# Spooky_Sound_System.net
KiCad netlist of a schematic drawn in EAGLE
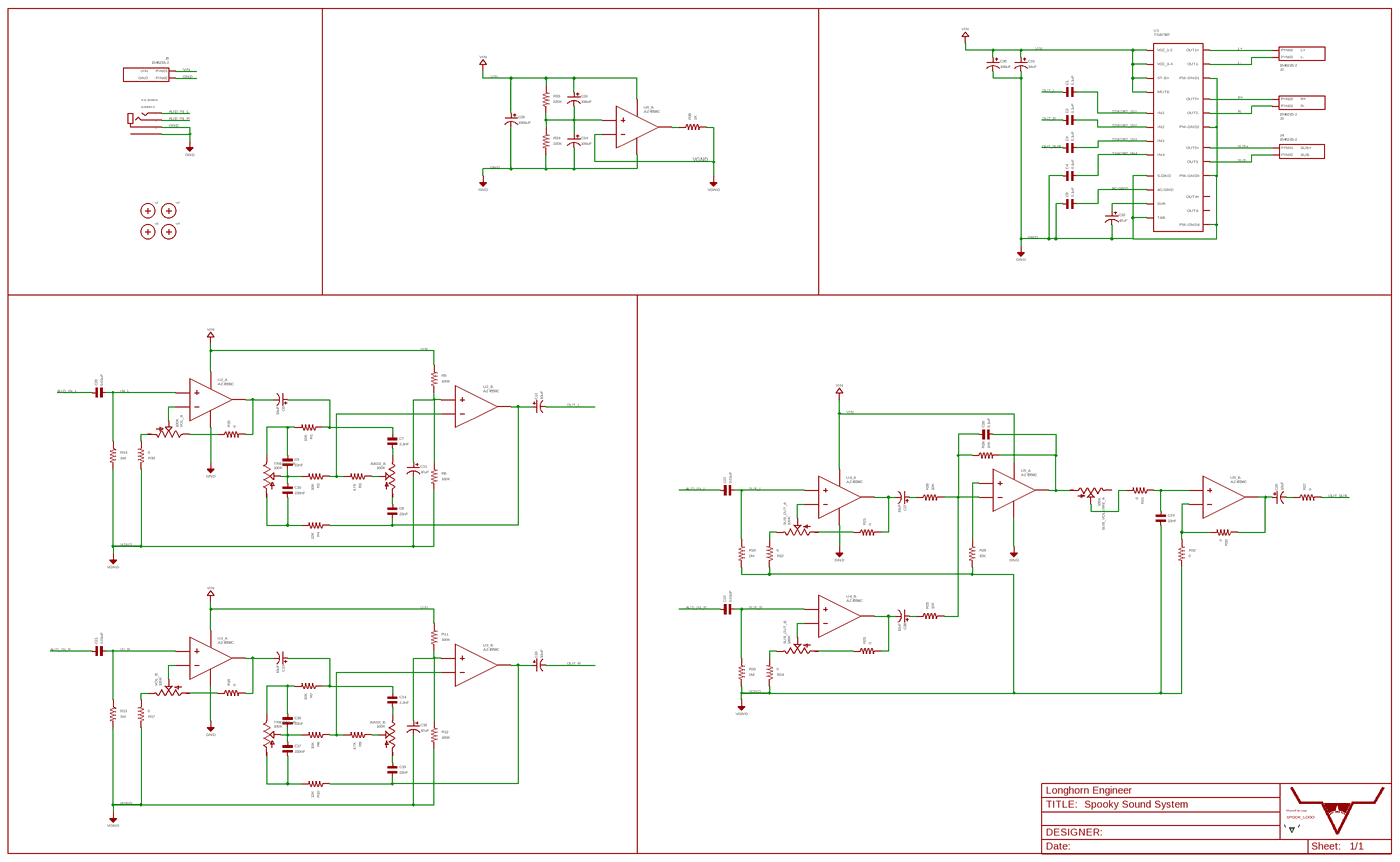
[diagram p0: schematic, sheet 1, overview]
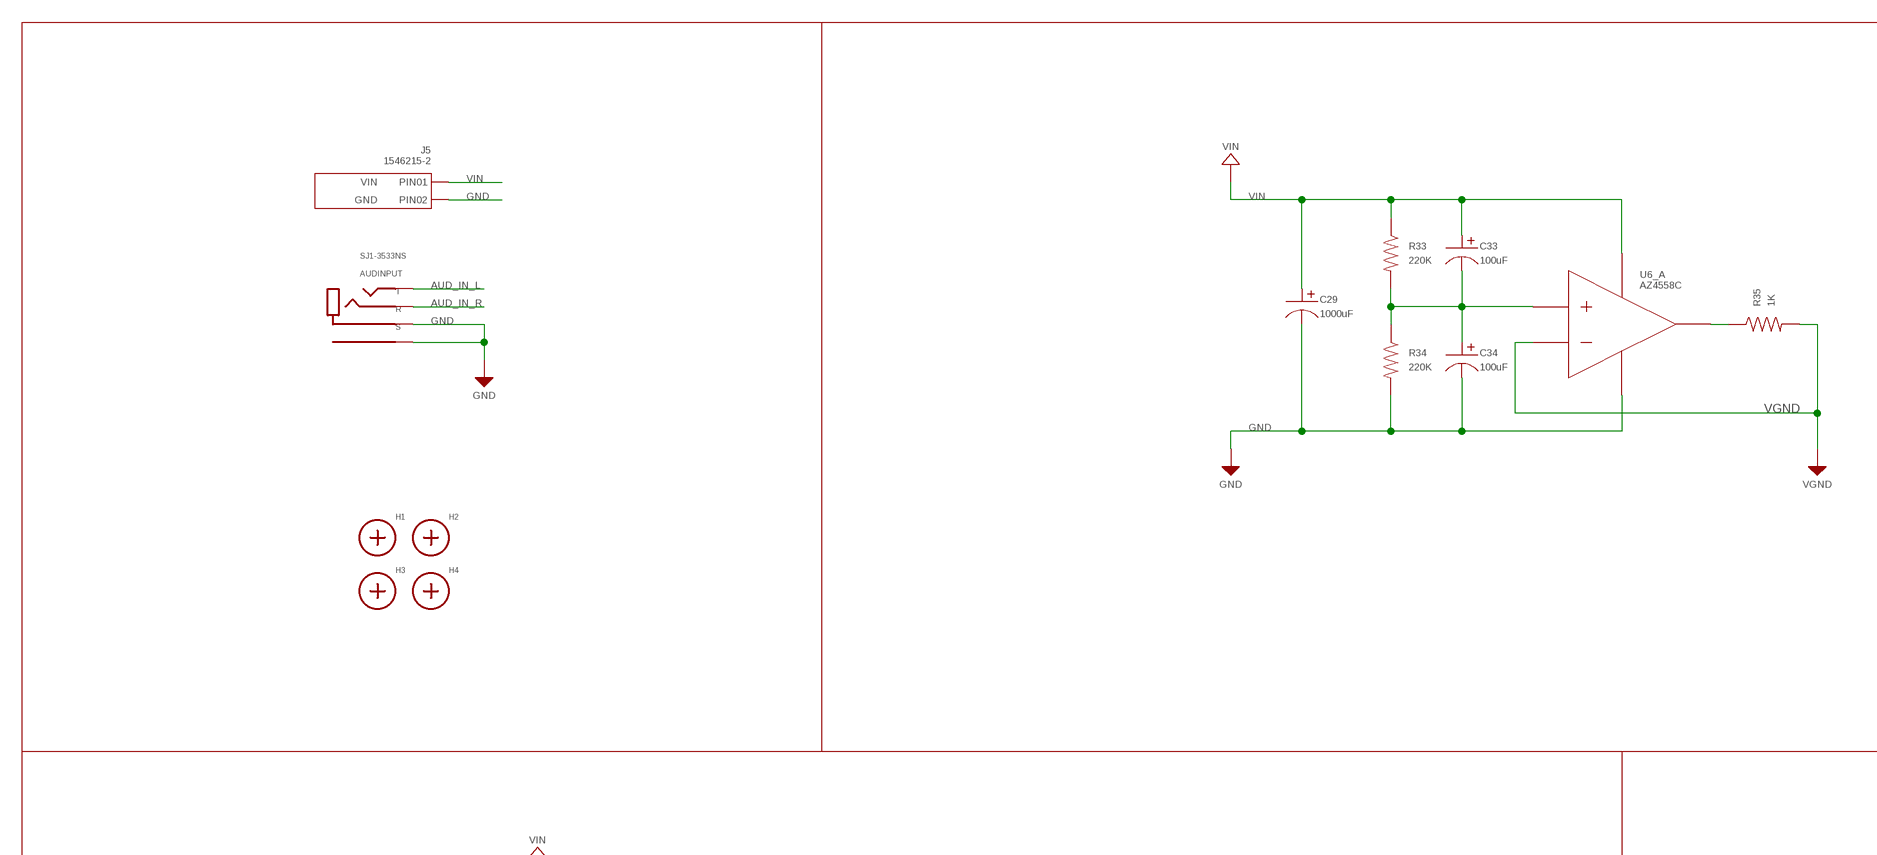
[diagram p1: schematic, sheet 1, part 1 of 4]
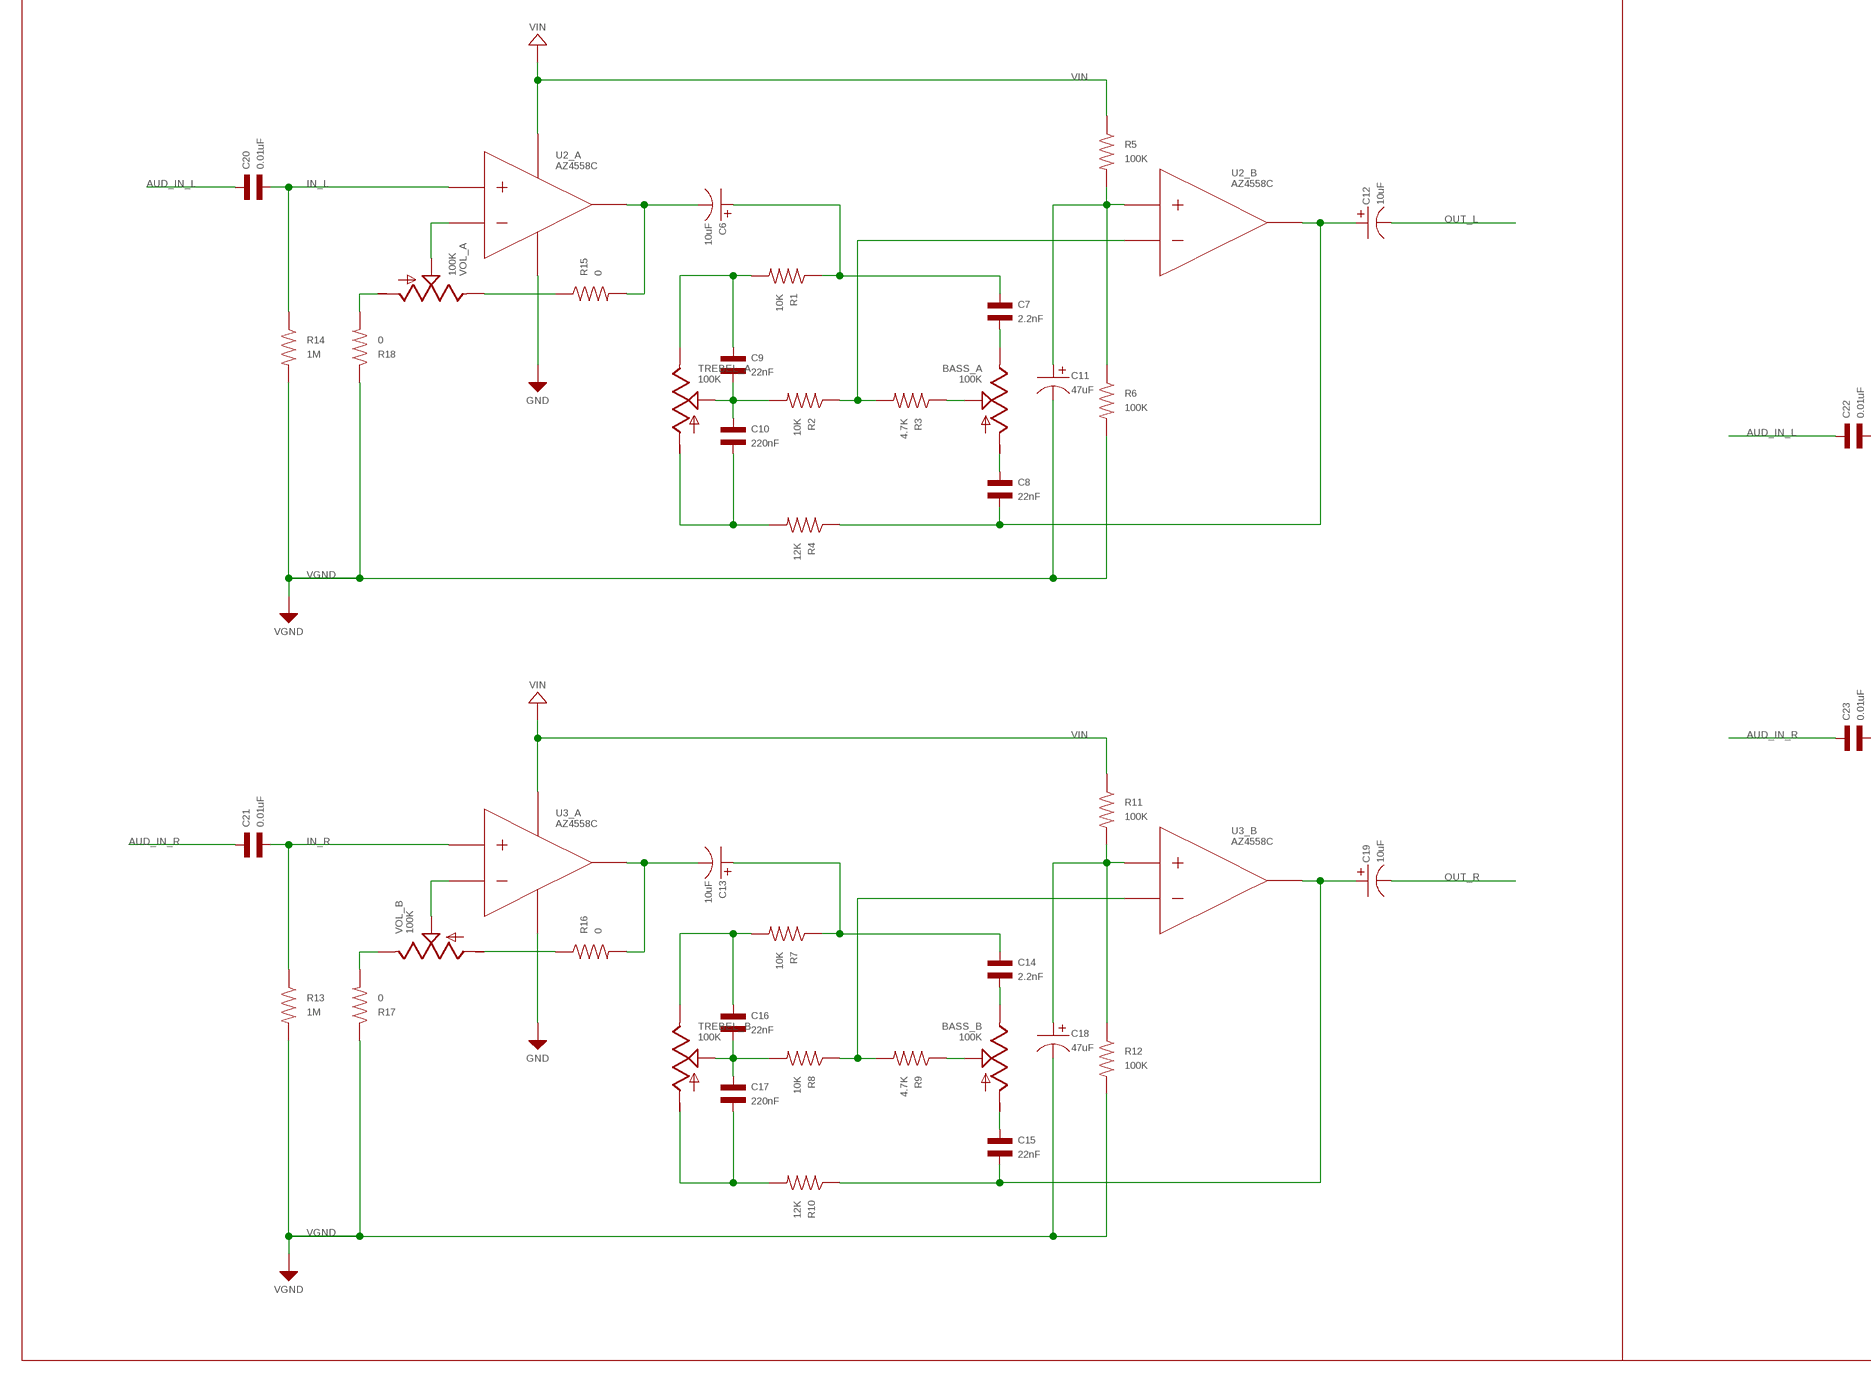
[diagram p2: schematic, sheet 1, part 2 of 4]
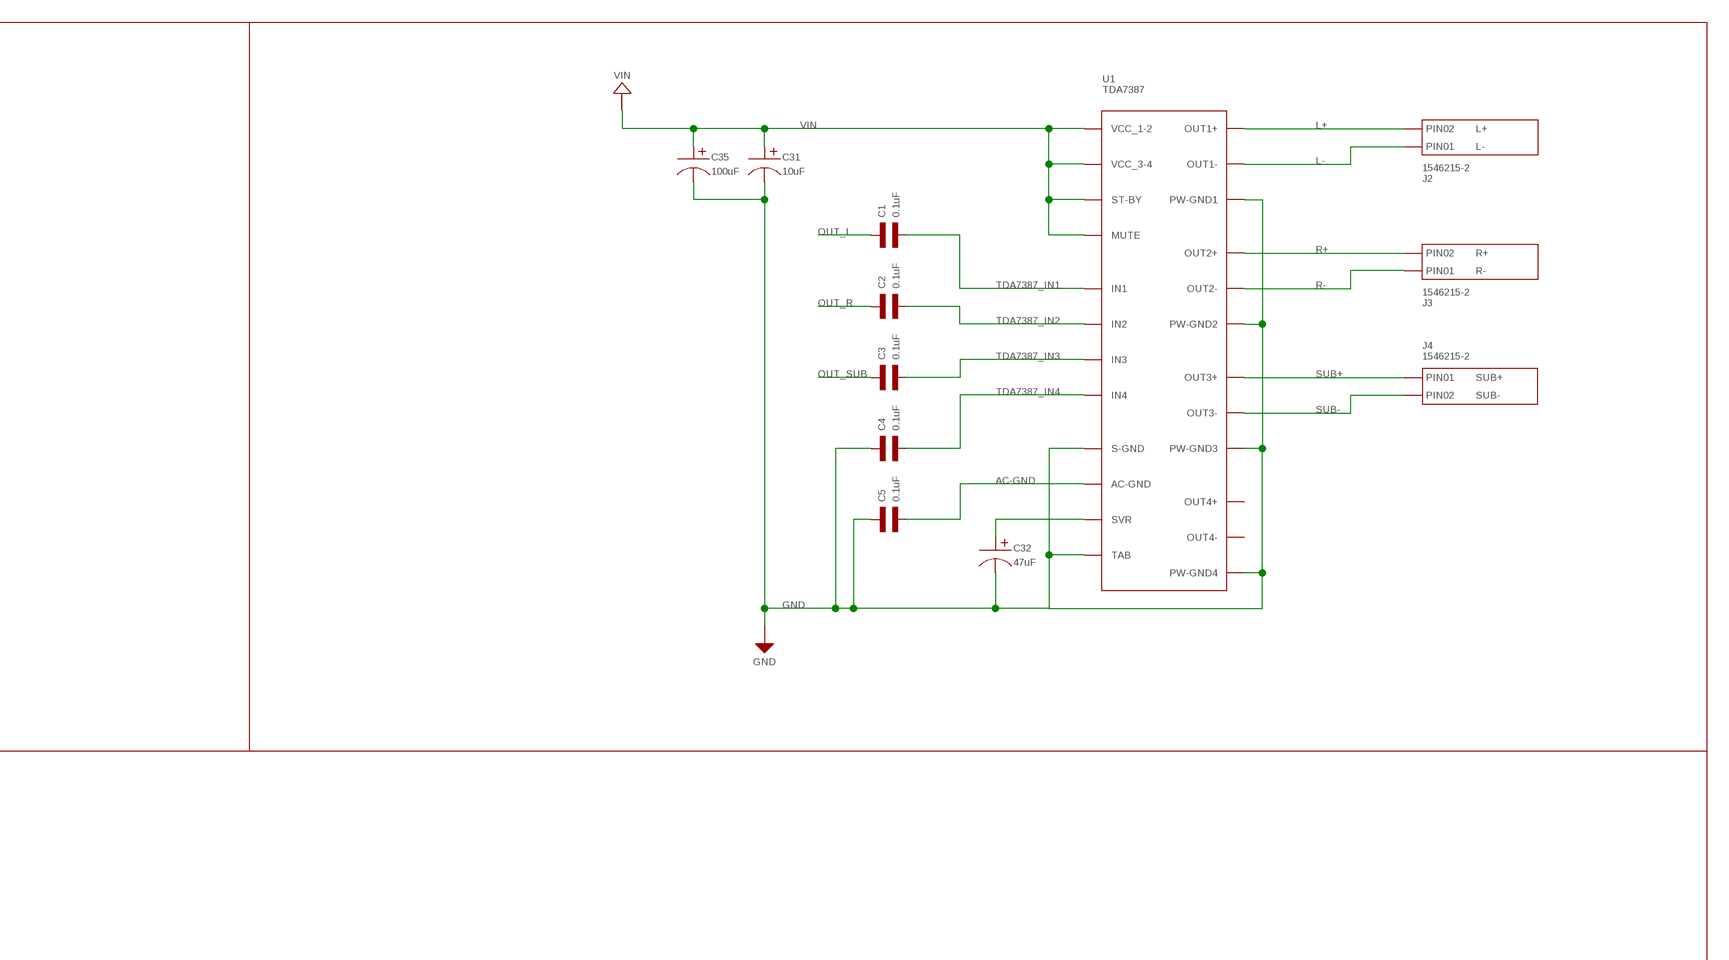
[diagram p3: schematic, sheet 1, part 3 of 4]
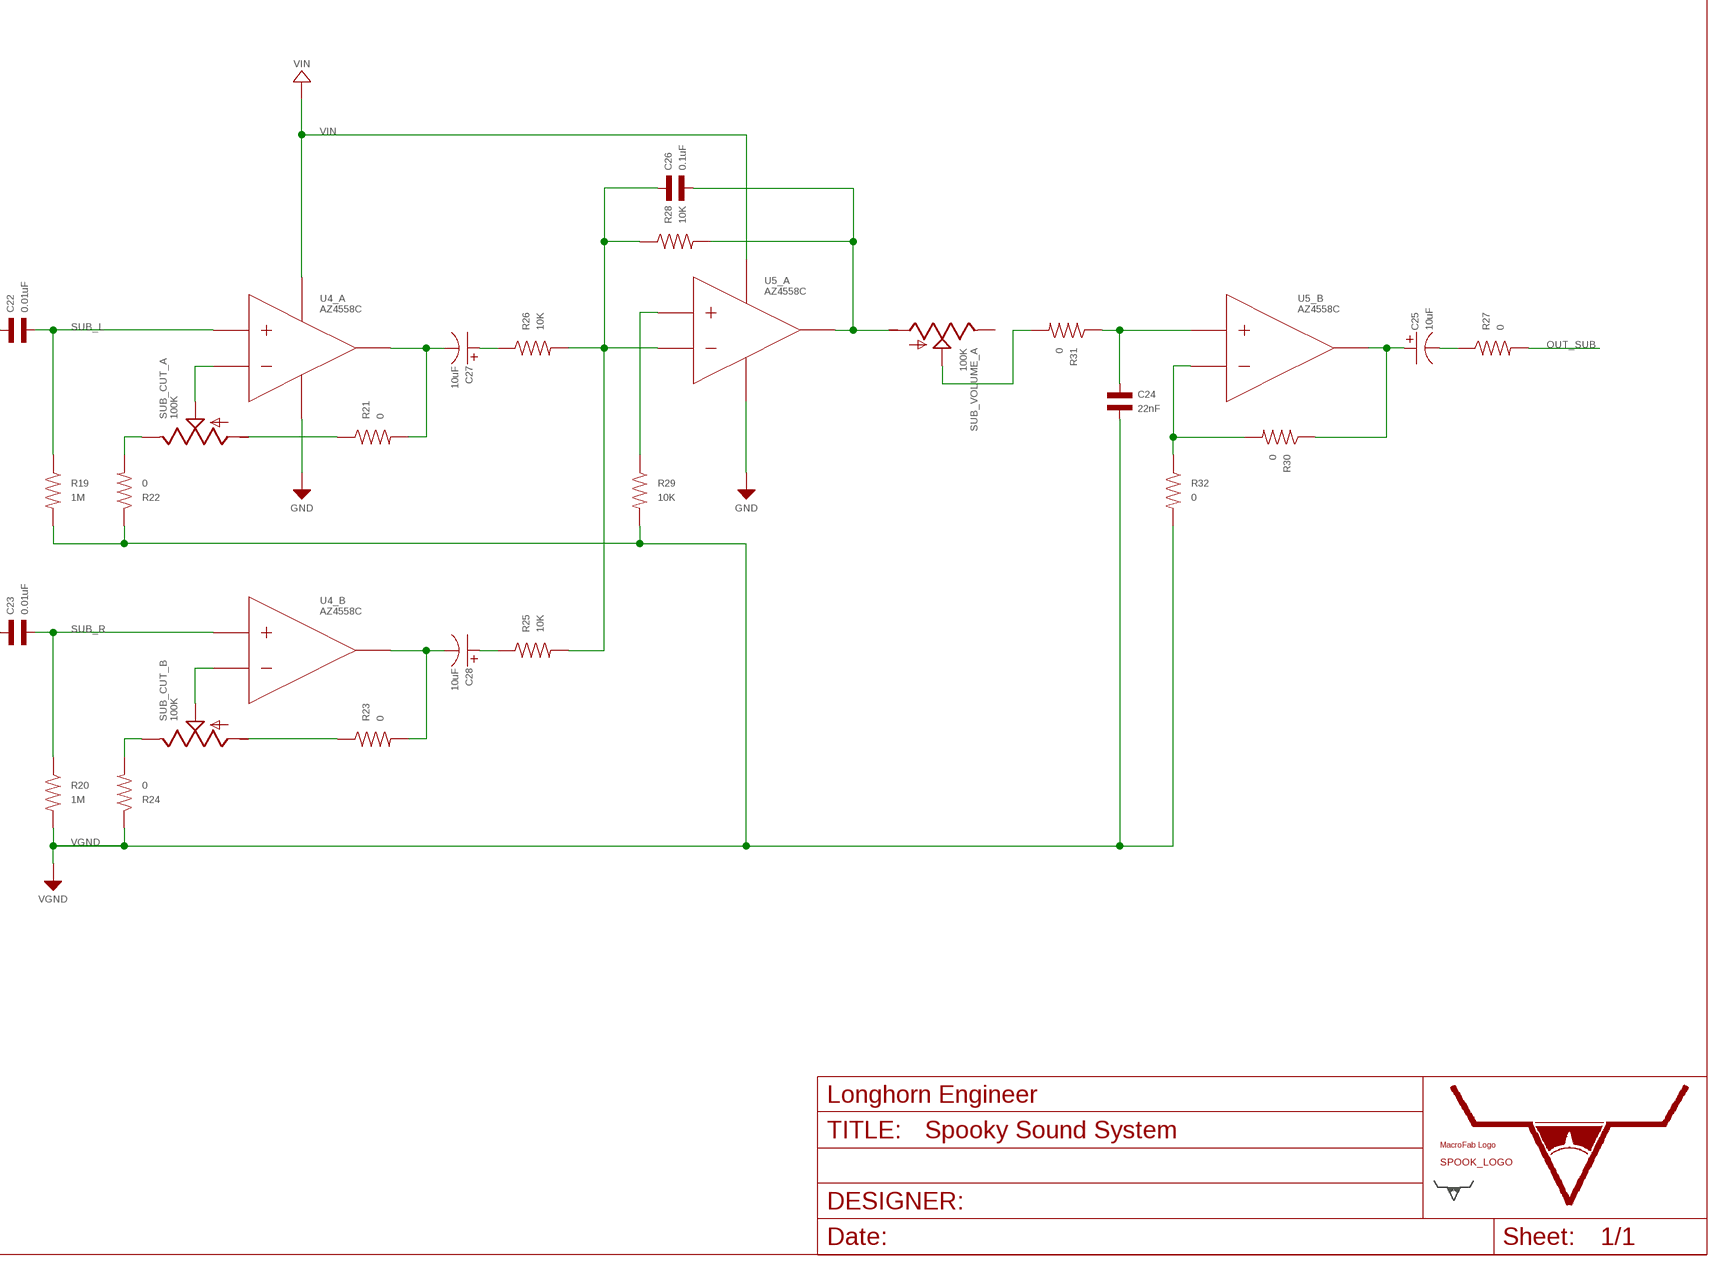
[diagram p4: schematic, sheet 1, part 4 of 4]

(export (version "E")
  (design (tool "Eeschema 10.0.6"))
  (components
    (comp (ref "AUDINPUT")
      (value "SJ1-3533NS")
      (footprint "eagle-import:SJ1-3533NS")
      (libsource (lib "eagle-import") (part "TRS_SHIELD_JACK_SJ1-3533NS"))
    )
    (comp (ref "BASS")
      (value "100K")
      (footprint "eagle-import:DUAL_TAPER_POTENTIOMETER")
      (libsource (lib "eagle-import") (part "DUAL_TAPER_POTENTIOMETER"))
    )
    (comp (ref "C1")
      (value "0.1uF")
      (footprint "eagle-import:C1206")
      (fields (field (name "MPN") "VJ1206Y104JXBTW1BC"))
      (libsource (lib "eagle-import") (part "CAPACITOR_NP_1206"))
    )
    (comp (ref "C2")
      (value "0.1uF")
      (footprint "eagle-import:C1206")
      (fields (field (name "MPN") "VJ1206Y104JXBTW1BC"))
      (libsource (lib "eagle-import") (part "CAPACITOR_NP_1206"))
    )
    (comp (ref "C3")
      (value "0.1uF")
      (footprint "eagle-import:C1206")
      (fields (field (name "MPN") "VJ1206Y104JXBTW1BC"))
      (libsource (lib "eagle-import") (part "CAPACITOR_NP_1206"))
    )
    (comp (ref "C4")
      (value "0.1uF")
      (footprint "eagle-import:C1206")
      (fields (field (name "MPN") "VJ1206Y104JXBTW1BC"))
      (libsource (lib "eagle-import") (part "CAPACITOR_NP_1206"))
    )
    (comp (ref "C5")
      (value "0.1uF")
      (footprint "eagle-import:C1206")
      (fields (field (name "MPN") "VJ1206Y104JXBTW1BC"))
      (libsource (lib "eagle-import") (part "CAPACITOR_NP_1206"))
    )
    (comp (ref "C6")
      (value "10uF")
      (footprint "eagle-import:CP4MM")
      (fields (field (name "MPN") "MF-CAP-4MM-10uF"))
      (libsource (lib "eagle-import") (part "CAPACITOR_P_4MM"))
    )
    (comp (ref "C7")
      (value "2.2nF")
      (footprint "eagle-import:C0805")
      (libsource (lib "eagle-import") (part "CAPACITOR_NP_0805"))
    )
    (comp (ref "C8")
      (value "22nF")
      (footprint "eagle-import:C0805")
      (libsource (lib "eagle-import") (part "CAPACITOR_NP_0805"))
    )
    (comp (ref "C9")
      (value "22nF")
      (footprint "eagle-import:C0805")
      (libsource (lib "eagle-import") (part "CAPACITOR_NP_0805"))
    )
    (comp (ref "C10")
      (value "220nF")
      (footprint "eagle-import:C0805")
      (libsource (lib "eagle-import") (part "CAPACITOR_NP_0805"))
    )
    (comp (ref "C11")
      (value "47uF")
      (footprint "eagle-import:CP6.3MM")
      (fields (field (name "MPN") "MF-CAP-6.3MM-47uF"))
      (libsource (lib "eagle-import") (part "CAPACITOR_P_6.3MM"))
    )
    (comp (ref "C12")
      (value "10uF")
      (footprint "eagle-import:CP4MM")
      (fields (field (name "MPN") "MF-CAP-4MM-10uF"))
      (libsource (lib "eagle-import") (part "CAPACITOR_P_4MM"))
    )
    (comp (ref "C13")
      (value "10uF")
      (footprint "eagle-import:CP4MM")
      (fields (field (name "MPN") "MF-CAP-4MM-10uF"))
      (libsource (lib "eagle-import") (part "CAPACITOR_P_4MM"))
    )
    (comp (ref "C14")
      (value "2.2nF")
      (footprint "eagle-import:C0805")
      (libsource (lib "eagle-import") (part "CAPACITOR_NP_0805"))
    )
    (comp (ref "C15")
      (value "22nF")
      (footprint "eagle-import:C0805")
      (libsource (lib "eagle-import") (part "CAPACITOR_NP_0805"))
    )
    (comp (ref "C16")
      (value "22nF")
      (footprint "eagle-import:C0805")
      (libsource (lib "eagle-import") (part "CAPACITOR_NP_0805"))
    )
    (comp (ref "C17")
      (value "220nF")
      (footprint "eagle-import:C0805")
      (libsource (lib "eagle-import") (part "CAPACITOR_NP_0805"))
    )
    (comp (ref "C18")
      (value "47uF")
      (footprint "eagle-import:CP6.3MM")
      (fields (field (name "MPN") "MF-CAP-6.3MM-47uF"))
      (libsource (lib "eagle-import") (part "CAPACITOR_P_6.3MM"))
    )
    (comp (ref "C19")
      (value "10uF")
      (footprint "eagle-import:CP4MM")
      (fields (field (name "MPN") "MF-CAP-4MM-10uF"))
      (libsource (lib "eagle-import") (part "CAPACITOR_P_4MM"))
    )
    (comp (ref "C20")
      (value "0.01uF")
      (footprint "eagle-import:C1210")
      (fields (field (name "MPN") "CB017E0103KBA"))
      (libsource (lib "eagle-import") (part "CAPACITOR_NP_1210"))
    )
    (comp (ref "C21")
      (value "0.01uF")
      (footprint "eagle-import:C1210")
      (fields (field (name "MPN") "CB017E0103KBA"))
      (libsource (lib "eagle-import") (part "CAPACITOR_NP_1210"))
    )
    (comp (ref "C22")
      (value "0.01uF")
      (footprint "eagle-import:C1210")
      (fields (field (name "MPN") "CB017E0103KBA"))
      (libsource (lib "eagle-import") (part "CAPACITOR_NP_1210"))
    )
    (comp (ref "C23")
      (value "0.01uF")
      (footprint "eagle-import:C1210")
      (fields (field (name "MPN") "CB017E0103KBA"))
      (libsource (lib "eagle-import") (part "CAPACITOR_NP_1210"))
    )
    (comp (ref "C24")
      (value "22nF")
      (footprint "eagle-import:C0805")
      (libsource (lib "eagle-import") (part "CAPACITOR_NP_0805"))
    )
    (comp (ref "C25")
      (value "10uF")
      (footprint "eagle-import:CP4MM")
      (fields (field (name "MPN") "MF-CAP-4MM-10uF"))
      (libsource (lib "eagle-import") (part "CAPACITOR_P_4MM"))
    )
    (comp (ref "C26")
      (value "0.1uF")
      (footprint "eagle-import:C0805")
      (libsource (lib "eagle-import") (part "CAPACITOR_NP_0805"))
    )
    (comp (ref "C27")
      (value "10uF")
      (footprint "eagle-import:CP4MM")
      (fields (field (name "MPN") "MF-CAP-4MM-10uF"))
      (libsource (lib "eagle-import") (part "CAPACITOR_P_4MM"))
    )
    (comp (ref "C28")
      (value "10uF")
      (footprint "eagle-import:CP4MM")
      (fields (field (name "MPN") "MF-CAP-4MM-10uF"))
      (libsource (lib "eagle-import") (part "CAPACITOR_P_4MM"))
    )
    (comp (ref "C29")
      (value "1000uF")
      (footprint "eagle-import:CP12.5MM")
      (fields (field (name "MPN") "MF-CAP-12.5MM-1000uF"))
      (libsource (lib "eagle-import") (part "CAPACITOR_P_12.5MM"))
    )
    (comp (ref "C31")
      (value "10uF")
      (footprint "eagle-import:CP4MM")
      (fields (field (name "MPN") "MF-CAP-4MM-10uF"))
      (libsource (lib "eagle-import") (part "CAPACITOR_P_4MM"))
    )
    (comp (ref "C32")
      (value "47uF")
      (footprint "eagle-import:CP6.3MM")
      (fields (field (name "MPN") "MF-CAP-6.3MM-47uF"))
      (libsource (lib "eagle-import") (part "CAPACITOR_P_6.3MM"))
    )
    (comp (ref "C33")
      (value "100uF")
      (footprint "eagle-import:CP6.3MM")
      (fields (field (name "MPN") "MF-CAP-6.3MM-100uF"))
      (libsource (lib "eagle-import") (part "CAPACITOR_P_6.3MM"))
    )
    (comp (ref "C34")
      (value "100uF")
      (footprint "eagle-import:CP6.3MM")
      (fields (field (name "MPN") "MF-CAP-6.3MM-100uF"))
      (libsource (lib "eagle-import") (part "CAPACITOR_P_6.3MM"))
    )
    (comp (ref "C35")
      (value "100uF")
      (footprint "eagle-import:CP6.3MM")
      (fields (field (name "MPN") "MF-CAP-6.3MM-100uF"))
      (libsource (lib "eagle-import") (part "CAPACITOR_P_6.3MM"))
    )
    (comp (ref "H1")
      (value "MOUNT_HOLE150MIL")
      (footprint "eagle-import:MOUNT_HOLE_150MIL")
      (libsource (lib "eagle-import") (part "MOUNT_HOLE150MIL"))
    )
    (comp (ref "H2")
      (value "MOUNT_HOLE150MIL")
      (footprint "eagle-import:MOUNT_HOLE_150MIL")
      (libsource (lib "eagle-import") (part "MOUNT_HOLE150MIL"))
    )
    (comp (ref "H3")
      (value "MOUNT_HOLE150MIL")
      (footprint "eagle-import:MOUNT_HOLE_150MIL")
      (libsource (lib "eagle-import") (part "MOUNT_HOLE150MIL"))
    )
    (comp (ref "H4")
      (value "MOUNT_HOLE150MIL")
      (footprint "eagle-import:MOUNT_HOLE_150MIL")
      (libsource (lib "eagle-import") (part "MOUNT_HOLE150MIL"))
    )
    (comp (ref "J2")
      (value "1546215-2")
      (footprint "eagle-import:1546215-2")
      (fields (field (name "LABEL01") "L-") (field (name "LABEL02") "L+"))
      (libsource (lib "eagle-import") (part "CON_01X02_1546215-2"))
    )
    (comp (ref "J3")
      (value "1546215-2")
      (footprint "eagle-import:1546215-2")
      (fields (field (name "LABEL01") "R-") (field (name "LABEL02") "R+"))
      (libsource (lib "eagle-import") (part "CON_01X02_1546215-2"))
    )
    (comp (ref "J4")
      (value "1546215-2")
      (footprint "eagle-import:1546215-2")
      (fields (field (name "LABEL01") "SUB+") (field (name "LABEL02") "SUB-"))
      (libsource (lib "eagle-import") (part "CON_01X02_1546215-2"))
    )
    (comp (ref "J5")
      (value "1546215-2")
      (footprint "eagle-import:1546215-2")
      (fields (field (name "LABEL01") "VIN") (field (name "LABEL02") "GND"))
      (libsource (lib "eagle-import") (part "CON_01X02_1546215-2"))
    )
    (comp (ref "LOGO1")
      (value "SPOOKY_LOGOSPOOKY_LOGO")
      (footprint "eagle-import:SPOOKY_LOGO")
      (libsource (lib "eagle-import") (part "SPOOKY_LOGOSPOOKY_LOGO"))
    )
    (comp (ref "R1")
      (value "10K")
      (footprint "eagle-import:R0805")
      (libsource (lib "eagle-import") (part "RESISTOR_0805"))
    )
    (comp (ref "R2")
      (value "10K")
      (footprint "eagle-import:R0805")
      (libsource (lib "eagle-import") (part "RESISTOR_0805"))
    )
    (comp (ref "R3")
      (value "4.7K")
      (footprint "eagle-import:R0805")
      (libsource (lib "eagle-import") (part "RESISTOR_0805"))
    )
    (comp (ref "R4")
      (value "12K")
      (footprint "eagle-import:R0805")
      (libsource (lib "eagle-import") (part "RESISTOR_0805"))
    )
    (comp (ref "R5")
      (value "100K")
      (footprint "eagle-import:R0805")
      (libsource (lib "eagle-import") (part "RESISTOR_0805"))
    )
    (comp (ref "R6")
      (value "100K")
      (footprint "eagle-import:R0805")
      (libsource (lib "eagle-import") (part "RESISTOR_0805"))
    )
    (comp (ref "R7")
      (value "10K")
      (footprint "eagle-import:R0805")
      (libsource (lib "eagle-import") (part "RESISTOR_0805"))
    )
    (comp (ref "R8")
      (value "10K")
      (footprint "eagle-import:R0805")
      (libsource (lib "eagle-import") (part "RESISTOR_0805"))
    )
    (comp (ref "R9")
      (value "4.7K")
      (footprint "eagle-import:R0805")
      (libsource (lib "eagle-import") (part "RESISTOR_0805"))
    )
    (comp (ref "R10")
      (value "12K")
      (footprint "eagle-import:R0805")
      (libsource (lib "eagle-import") (part "RESISTOR_0805"))
    )
    (comp (ref "R11")
      (value "100K")
      (footprint "eagle-import:R0805")
      (libsource (lib "eagle-import") (part "RESISTOR_0805"))
    )
    (comp (ref "R12")
      (value "100K")
      (footprint "eagle-import:R0805")
      (libsource (lib "eagle-import") (part "RESISTOR_0805"))
    )
    (comp (ref "R13")
      (value "1M")
      (footprint "eagle-import:R0805")
      (libsource (lib "eagle-import") (part "RESISTOR_0805"))
    )
    (comp (ref "R14")
      (value "1M")
      (footprint "eagle-import:R0805")
      (libsource (lib "eagle-import") (part "RESISTOR_0805"))
    )
    (comp (ref "R15")
      (value "0")
      (footprint "eagle-import:R0805")
      (libsource (lib "eagle-import") (part "RESISTOR_0805"))
    )
    (comp (ref "R16")
      (value "0")
      (footprint "eagle-import:R0805")
      (libsource (lib "eagle-import") (part "RESISTOR_0805"))
    )
    (comp (ref "R17")
      (value "0")
      (footprint "eagle-import:R0805")
      (libsource (lib "eagle-import") (part "RESISTOR_0805"))
    )
    (comp (ref "R18")
      (value "0")
      (footprint "eagle-import:R0805")
      (libsource (lib "eagle-import") (part "RESISTOR_0805"))
    )
    (comp (ref "R19")
      (value "1M")
      (footprint "eagle-import:R0805")
      (libsource (lib "eagle-import") (part "RESISTOR_0805"))
    )
    (comp (ref "R20")
      (value "1M")
      (footprint "eagle-import:R0805")
      (libsource (lib "eagle-import") (part "RESISTOR_0805"))
    )
    (comp (ref "R21")
      (value "0")
      (footprint "eagle-import:R0805")
      (libsource (lib "eagle-import") (part "RESISTOR_0805"))
    )
    (comp (ref "R22")
      (value "0")
      (footprint "eagle-import:R0805")
      (libsource (lib "eagle-import") (part "RESISTOR_0805"))
    )
    (comp (ref "R23")
      (value "0")
      (footprint "eagle-import:R0805")
      (libsource (lib "eagle-import") (part "RESISTOR_0805"))
    )
    (comp (ref "R24")
      (value "0")
      (footprint "eagle-import:R0805")
      (libsource (lib "eagle-import") (part "RESISTOR_0805"))
    )
    (comp (ref "R25")
      (value "10K")
      (footprint "eagle-import:R0805")
      (libsource (lib "eagle-import") (part "RESISTOR_0805"))
    )
    (comp (ref "R26")
      (value "10K")
      (footprint "eagle-import:R0805")
      (libsource (lib "eagle-import") (part "RESISTOR_0805"))
    )
    (comp (ref "R27")
      (value "0")
      (footprint "eagle-import:R0805")
      (libsource (lib "eagle-import") (part "RESISTOR_0805"))
    )
    (comp (ref "R28")
      (value "10K")
      (footprint "eagle-import:R0805")
      (libsource (lib "eagle-import") (part "RESISTOR_0805"))
    )
    (comp (ref "R29")
      (value "10K")
      (footprint "eagle-import:R0805")
      (libsource (lib "eagle-import") (part "RESISTOR_0805"))
    )
    (comp (ref "R30")
      (value "0")
      (footprint "eagle-import:R0805")
      (libsource (lib "eagle-import") (part "RESISTOR_0805"))
    )
    (comp (ref "R31")
      (value "0")
      (footprint "eagle-import:R0805")
      (libsource (lib "eagle-import") (part "RESISTOR_0805"))
    )
    (comp (ref "R32")
      (value "0")
      (footprint "eagle-import:R0805")
      (fields (field (name "POPULATE") "0"))
      (libsource (lib "eagle-import") (part "RESISTOR_0805"))
    )
    (comp (ref "R33")
      (value "220K")
      (footprint "eagle-import:R0805")
      (libsource (lib "eagle-import") (part "RESISTOR_0805"))
    )
    (comp (ref "R34")
      (value "220K")
      (footprint "eagle-import:R0805")
      (libsource (lib "eagle-import") (part "RESISTOR_0805"))
    )
    (comp (ref "R35")
      (value "1K")
      (footprint "eagle-import:R0805")
      (libsource (lib "eagle-import") (part "RESISTOR_0805"))
    )
    (comp (ref "SUB_CUT")
      (value "100K")
      (footprint "eagle-import:DUAL_TAPER_POTENTIOMETER")
      (libsource (lib "eagle-import") (part "DUAL_TAPER_POTENTIOMETER"))
    )
    (comp (ref "SUB_VOLUME")
      (value "100K")
      (footprint "eagle-import:DUAL_TAPER_POTENTIOMETER")
      (libsource (lib "eagle-import") (part "DUAL_TAPER_POTENTIOMETER"))
    )
    (comp (ref "TREBEL")
      (value "100K")
      (footprint "eagle-import:DUAL_TAPER_POTENTIOMETER")
      (libsource (lib "eagle-import") (part "DUAL_TAPER_POTENTIOMETER"))
    )
    (comp (ref "U$17")
      (value "LHE_FRAME")
      (footprint "eagle-import:LHE_FRAME")
      (fields (field (name "DNAME") "Parker Dillmann") (field (name "REVNUM") "REV: 1"))
      (libsource (lib "eagle-import") (part "LHE_FRAME"))
    )
    (comp (ref "U$18")
      (value "LHE_LOGOLHE_LOGO")
      (footprint "eagle-import:LHE_LOGO")
      (libsource (lib "eagle-import") (part "LHE_LOGOLHE_LOGO"))
    )
    (comp (ref "U$19")
      (value "MF_LOGOLOGO_TEXT")
      (footprint "eagle-import:MF_LOGO_TEXT")
      (libsource (lib "eagle-import") (part "MF_LOGOLOGO_TEXT"))
    )
    (comp (ref "U1")
      (value "TDA7387")
      (footprint "eagle-import:TDA7387-FLEXIWATT-25")
      (libsource (lib "eagle-import") (part "TDA7387"))
    )
    (comp (ref "U2")
      (value "AZ4558C")
      (footprint "eagle-import:AZ4558C_SOIC-8")
      (libsource (lib "eagle-import") (part "AZ4558C"))
    )
    (comp (ref "U3")
      (value "AZ4558C")
      (footprint "eagle-import:AZ4558C_SOIC-8")
      (libsource (lib "eagle-import") (part "AZ4558C"))
    )
    (comp (ref "U4")
      (value "AZ4558C")
      (footprint "eagle-import:AZ4558C_SOIC-8")
      (libsource (lib "eagle-import") (part "AZ4558C"))
    )
    (comp (ref "U5")
      (value "AZ4558C")
      (footprint "eagle-import:AZ4558C_SOIC-8")
      (libsource (lib "eagle-import") (part "AZ4558C"))
    )
    (comp (ref "U6")
      (value "AZ4558C")
      (footprint "eagle-import:AZ4558C_SOIC-8")
      (libsource (lib "eagle-import") (part "AZ4558C"))
    )
    (comp (ref "VOL")
      (value "100K")
      (footprint "eagle-import:DUAL_TAPER_POTENTIOMETER")
      (libsource (lib "eagle-import") (part "DUAL_TAPER_POTENTIOMETER"))
    )
  )
  (nets
    (net (code "1") (name "/AC-GND") (class "Default")
      (node (ref "C5") (pin "P$2") (pinfunction "P$2_P$2") (pintype "passive"))
      (node (ref "U1") (pin "P$16") (pinfunction "AC-GND_P$16") (pintype "bidirectional"))
    )
    (net (code "2") (name "/AUD_IN_L") (class "Default")
      (node (ref "AUDINPUT") (pin "2_A") (pinfunction "T_2_A") (pintype "bidirectional"))
      (node (ref "AUDINPUT") (pin "2_B") (pinfunction "T_2_B") (pintype "bidirectional"))
      (node (ref "C20") (pin "P$1") (pinfunction "P$1_P$1") (pintype "passive"))
      (node (ref "C22") (pin "P$1") (pinfunction "P$1_P$1") (pintype "passive"))
    )
    (net (code "3") (name "/AUD_IN_R") (class "Default")
      (node (ref "AUDINPUT") (pin "3_A") (pinfunction "R_3_A") (pintype "bidirectional"))
      (node (ref "AUDINPUT") (pin "3_B") (pinfunction "R_3_B") (pintype "bidirectional"))
      (node (ref "C21") (pin "P$1") (pinfunction "P$1_P$1") (pintype "passive"))
      (node (ref "C23") (pin "P$1") (pinfunction "P$1_P$1") (pintype "passive"))
    )
    (net (code "4") (name "/IN_L") (class "Default")
      (node (ref "C20") (pin "P$2") (pinfunction "P$2_P$2") (pintype "passive"))
      (node (ref "R14") (pin "P$1") (pinfunction "P$1_P$1") (pintype "passive"))
      (node (ref "U2") (pin "3") (pinfunction "INPUT_1+_3") (pintype "bidirectional"))
    )
    (net (code "5") (name "/IN_R") (class "Default")
      (node (ref "C21") (pin "P$2") (pinfunction "P$2_P$2") (pintype "passive"))
      (node (ref "R13") (pin "P$1") (pinfunction "P$1_P$1") (pintype "passive"))
      (node (ref "U3") (pin "3") (pinfunction "INPUT_1+_3") (pintype "bidirectional"))
    )
    (net (code "6") (name "/L+") (class "Default")
      (node (ref "J2") (pin "P$2") (pinfunction "PIN2_P$2") (pintype "bidirectional"))
      (node (ref "U1") (pin "P$9") (pinfunction "OUT1+_P$9") (pintype "bidirectional"))
    )
    (net (code "7") (name "/L-") (class "Default")
      (node (ref "J2") (pin "P$1") (pinfunction "PIN1_P$1") (pintype "bidirectional"))
      (node (ref "U1") (pin "P$7") (pinfunction "OUT1-_P$7") (pintype "bidirectional"))
    )
    (net (code "8") (name "/OUT_L") (class "Default")
      (node (ref "C1") (pin "P$1") (pinfunction "P$1_P$1") (pintype "passive"))
      (node (ref "C12") (pin "P$2") (pinfunction "P$2_P$2") (pintype "passive"))
    )
    (net (code "9") (name "/OUT_R") (class "Default")
      (node (ref "C19") (pin "P$2") (pinfunction "P$2_P$2") (pintype "passive"))
      (node (ref "C2") (pin "P$1") (pinfunction "P$1_P$1") (pintype "passive"))
    )
    (net (code "10") (name "/OUT_SUB") (class "Default")
      (node (ref "C3") (pin "P$1") (pinfunction "P$1_P$1") (pintype "passive"))
      (node (ref "R27") (pin "P$2") (pinfunction "P$2_P$2") (pintype "passive"))
    )
    (net (code "11") (name "/R+") (class "Default")
      (node (ref "J3") (pin "P$2") (pinfunction "PIN2_P$2") (pintype "bidirectional"))
      (node (ref "U1") (pin "P$5") (pinfunction "OUT2+_P$5") (pintype "bidirectional"))
    )
    (net (code "12") (name "/R-") (class "Default")
      (node (ref "J3") (pin "P$1") (pinfunction "PIN1_P$1") (pintype "bidirectional"))
      (node (ref "U1") (pin "P$3") (pinfunction "OUT2-_P$3") (pintype "bidirectional"))
    )
    (net (code "13") (name "/SUB+") (class "Default")
      (node (ref "J4") (pin "P$1") (pinfunction "PIN1_P$1") (pintype "bidirectional"))
      (node (ref "U1") (pin "P$17") (pinfunction "OUT3+_P$17") (pintype "bidirectional"))
    )
    (net (code "14") (name "/SUB-") (class "Default")
      (node (ref "J4") (pin "P$2") (pinfunction "PIN2_P$2") (pintype "bidirectional"))
      (node (ref "U1") (pin "P$19") (pinfunction "OUT3-_P$19") (pintype "bidirectional"))
    )
    (net (code "15") (name "/SUB_L") (class "Default")
      (node (ref "C22") (pin "P$2") (pinfunction "P$2_P$2") (pintype "passive"))
      (node (ref "R19") (pin "P$1") (pinfunction "P$1_P$1") (pintype "passive"))
      (node (ref "U4") (pin "3") (pinfunction "INPUT_1+_3") (pintype "bidirectional"))
    )
    (net (code "16") (name "/SUB_R") (class "Default")
      (node (ref "C23") (pin "P$2") (pinfunction "P$2_P$2") (pintype "passive"))
      (node (ref "R20") (pin "P$1") (pinfunction "P$1_P$1") (pintype "passive"))
      (node (ref "U4") (pin "5") (pinfunction "INPUT_2+_5") (pintype "bidirectional"))
    )
    (net (code "17") (name "/TDA7387_IN1") (class "Default")
      (node (ref "C1") (pin "P$2") (pinfunction "P$2_P$2") (pintype "passive"))
      (node (ref "U1") (pin "P$11") (pinfunction "IN1_P$11") (pintype "bidirectional"))
    )
    (net (code "18") (name "/TDA7387_IN2") (class "Default")
      (node (ref "C2") (pin "P$2") (pinfunction "P$2_P$2") (pintype "passive"))
      (node (ref "U1") (pin "P$12") (pinfunction "IN2_P$12") (pintype "bidirectional"))
    )
    (net (code "19") (name "/TDA7387_IN3") (class "Default")
      (node (ref "C3") (pin "P$2") (pinfunction "P$2_P$2") (pintype "passive"))
      (node (ref "U1") (pin "P$15") (pinfunction "IN3_P$15") (pintype "bidirectional"))
    )
    (net (code "20") (name "/TDA7387_IN4") (class "Default")
      (node (ref "C4") (pin "P$2") (pinfunction "P$2_P$2") (pintype "passive"))
      (node (ref "U1") (pin "P$14") (pinfunction "IN4_P$14") (pintype "bidirectional"))
    )
    (net (code "21") (name "GND") (class "Default")
      (node (ref "AUDINPUT") (pin "1_A") (pinfunction "S_1_A") (pintype "bidirectional"))
      (node (ref "AUDINPUT") (pin "1_B") (pinfunction "S_1_B") (pintype "bidirectional"))
      (node (ref "AUDINPUT") (pin "S1") (pinfunction "SHIELD_S1") (pintype "bidirectional"))
      (node (ref "AUDINPUT") (pin "S2") (pinfunction "SHIELD_S2") (pintype "bidirectional"))
      (node (ref "AUDINPUT") (pin "S3") (pinfunction "SHIELD_S3") (pintype "bidirectional"))
      (node (ref "AUDINPUT") (pin "S4") (pinfunction "SHIELD_S4") (pintype "bidirectional"))
      (node (ref "AUDINPUT") (pin "S5") (pinfunction "SHIELD_S5") (pintype "bidirectional"))
      (node (ref "AUDINPUT") (pin "S6") (pinfunction "SHIELD_S6") (pintype "bidirectional"))
      (node (ref "C29") (pin "P$2") (pinfunction "P$2_P$2") (pintype "passive"))
      (node (ref "C31") (pin "P$2") (pinfunction "P$2_P$2") (pintype "passive"))
      (node (ref "C32") (pin "P$2") (pinfunction "P$2_P$2") (pintype "passive"))
      (node (ref "C34") (pin "P$2") (pinfunction "P$2_P$2") (pintype "passive"))
      (node (ref "C35") (pin "P$2") (pinfunction "P$2_P$2") (pintype "passive"))
      (node (ref "C4") (pin "P$1") (pinfunction "P$1_P$1") (pintype "passive"))
      (node (ref "C5") (pin "P$1") (pinfunction "P$1_P$1") (pintype "passive"))
      (node (ref "J5") (pin "P$2") (pinfunction "PIN2_P$2") (pintype "bidirectional"))
      (node (ref "R34") (pin "P$2") (pinfunction "P$2_P$2") (pintype "passive"))
      (node (ref "U1") (pin "P$1") (pinfunction "TAB_P$1") (pintype "bidirectional"))
      (node (ref "U1") (pin "P$13") (pinfunction "S-GND_P$13") (pintype "bidirectional"))
      (node (ref "U1") (pin "P$18") (pinfunction "PW-GND3_P$18") (pintype "bidirectional"))
      (node (ref "U1") (pin "P$2") (pinfunction "PW-GND2_P$2") (pintype "bidirectional"))
      (node (ref "U1") (pin "P$24") (pinfunction "PW-GND4_P$24") (pintype "bidirectional"))
      (node (ref "U1") (pin "P$8") (pinfunction "PW-GND1_P$8") (pintype "bidirectional"))
      (node (ref "U2") (pin "4") (pinfunction "VEE_4") (pintype "bidirectional"))
      (node (ref "U3") (pin "4") (pinfunction "VEE_4") (pintype "bidirectional"))
      (node (ref "U4") (pin "4") (pinfunction "VEE_4") (pintype "bidirectional"))
      (node (ref "U5") (pin "4") (pinfunction "VEE_4") (pintype "bidirectional"))
      (node (ref "U6") (pin "4") (pinfunction "VEE_4") (pintype "bidirectional"))
    )
    (net (code "22") (name "Net-(BASSA-1)") (class "Default")
      (node (ref "BASS") (pin "1A") (pinfunction "1_1A") (pintype "bidirectional"))
      (node (ref "C7") (pin "P$2") (pinfunction "P$2_P$2") (pintype "passive"))
    )
    (net (code "23") (name "Net-(BASSA-2)") (class "Default")
      (node (ref "BASS") (pin "2A") (pinfunction "2_2A") (pintype "bidirectional"))
      (node (ref "R3") (pin "P$1") (pinfunction "P$1_P$1") (pintype "passive"))
    )
    (net (code "24") (name "Net-(BASSA-3)") (class "Default")
      (node (ref "BASS") (pin "3A") (pinfunction "3_3A") (pintype "bidirectional"))
      (node (ref "C8") (pin "P$1") (pinfunction "P$1_P$1") (pintype "passive"))
    )
    (net (code "25") (name "Net-(BASSB-1)") (class "Default")
      (node (ref "BASS") (pin "1B") (pinfunction "1_1B") (pintype "bidirectional"))
      (node (ref "C14") (pin "P$2") (pinfunction "P$2_P$2") (pintype "passive"))
    )
    (net (code "26") (name "Net-(BASSB-2)") (class "Default")
      (node (ref "BASS") (pin "2B") (pinfunction "2_2B") (pintype "bidirectional"))
      (node (ref "R9") (pin "P$1") (pinfunction "P$1_P$1") (pintype "passive"))
    )
    (net (code "27") (name "Net-(BASSB-3)") (class "Default")
      (node (ref "BASS") (pin "3B") (pinfunction "3_3B") (pintype "bidirectional"))
      (node (ref "C15") (pin "P$1") (pinfunction "P$1_P$1") (pintype "passive"))
    )
    (net (code "28") (name "Net-(C6-PadP$1)") (class "Default")
      (node (ref "C6") (pin "P$1") (pinfunction "P$1_P$1") (pintype "passive"))
      (node (ref "C7") (pin "P$1") (pinfunction "P$1_P$1") (pintype "passive"))
      (node (ref "R1") (pin "P$1") (pinfunction "P$1_P$1") (pintype "passive"))
    )
    (net (code "29") (name "Net-(C13-PadP$1)") (class "Default")
      (node (ref "C13") (pin "P$1") (pinfunction "P$1_P$1") (pintype "passive"))
      (node (ref "C14") (pin "P$1") (pinfunction "P$1_P$1") (pintype "passive"))
      (node (ref "R7") (pin "P$1") (pinfunction "P$1_P$1") (pintype "passive"))
    )
    (net (code "30") (name "Net-(C25-PadP$2)") (class "Default")
      (node (ref "C25") (pin "P$2") (pinfunction "P$2_P$2") (pintype "passive"))
      (node (ref "R27") (pin "P$1") (pinfunction "P$1_P$1") (pintype "passive"))
    )
    (net (code "31") (name "Net-(C27-PadP$1)") (class "Default")
      (node (ref "C27") (pin "P$1") (pinfunction "P$1_P$1") (pintype "passive"))
      (node (ref "R26") (pin "P$1") (pinfunction "P$1_P$1") (pintype "passive"))
    )
    (net (code "32") (name "Net-(C28-PadP$1)") (class "Default")
      (node (ref "C28") (pin "P$1") (pinfunction "P$1_P$1") (pintype "passive"))
      (node (ref "R25") (pin "P$1") (pinfunction "P$1_P$1") (pintype "passive"))
    )
    (net (code "33") (name "Net-(SUB_CUTA-1)") (class "Default")
      (node (ref "R22") (pin "P$2") (pinfunction "P$2_P$2") (pintype "passive"))
      (node (ref "SUB_CUT") (pin "1A") (pinfunction "1_1A") (pintype "bidirectional"))
    )
    (net (code "34") (name "Net-(SUB_CUTA-2)") (class "Default")
      (node (ref "SUB_CUT") (pin "2A") (pinfunction "2_2A") (pintype "bidirectional"))
      (node (ref "U4") (pin "2") (pinfunction "INPUT_1-_2") (pintype "bidirectional"))
    )
    (net (code "35") (name "Net-(SUB_CUTA-3)") (class "Default")
      (node (ref "R21") (pin "P$1") (pinfunction "P$1_P$1") (pintype "passive"))
      (node (ref "SUB_CUT") (pin "3A") (pinfunction "3_3A") (pintype "bidirectional"))
    )
    (net (code "36") (name "Net-(SUB_CUTB-1)") (class "Default")
      (node (ref "R24") (pin "P$2") (pinfunction "P$2_P$2") (pintype "passive"))
      (node (ref "SUB_CUT") (pin "1B") (pinfunction "1_1B") (pintype "bidirectional"))
    )
    (net (code "37") (name "Net-(SUB_CUTB-2)") (class "Default")
      (node (ref "SUB_CUT") (pin "2B") (pinfunction "2_2B") (pintype "bidirectional"))
      (node (ref "U4") (pin "6") (pinfunction "INPUT_2-_6") (pintype "bidirectional"))
    )
    (net (code "38") (name "Net-(SUB_CUTB-3)") (class "Default")
      (node (ref "R23") (pin "P$1") (pinfunction "P$1_P$1") (pintype "passive"))
      (node (ref "SUB_CUT") (pin "3B") (pinfunction "3_3B") (pintype "bidirectional"))
    )
    (net (code "39") (name "Net-(SUB_VOLUMEA-2)") (class "Default")
      (node (ref "R31") (pin "P$2") (pinfunction "P$2_P$2") (pintype "passive"))
      (node (ref "SUB_VOLUME") (pin "2A") (pinfunction "2_2A") (pintype "bidirectional"))
    )
    (net (code "40") (name "Net-(SUB_VOLUMEA-3)") (class "Default")
      (node (ref "C26") (pin "P$2") (pinfunction "P$2_P$2") (pintype "passive"))
      (node (ref "R28") (pin "P$2") (pinfunction "P$2_P$2") (pintype "passive"))
      (node (ref "SUB_VOLUME") (pin "3A") (pinfunction "3_3A") (pintype "bidirectional"))
      (node (ref "U5") (pin "1") (pinfunction "OUTPUT_1_1") (pintype "bidirectional"))
    )
    (net (code "41") (name "Net-(TREBELA-1)") (class "Default")
      (node (ref "C9") (pin "P$1") (pinfunction "P$1_P$1") (pintype "passive"))
      (node (ref "R1") (pin "P$2") (pinfunction "P$2_P$2") (pintype "passive"))
      (node (ref "TREBEL") (pin "1A") (pinfunction "1_1A") (pintype "bidirectional"))
    )
    (net (code "42") (name "Net-(TREBELA-2)") (class "Default")
      (node (ref "C10") (pin "P$1") (pinfunction "P$1_P$1") (pintype "passive"))
      (node (ref "C9") (pin "P$2") (pinfunction "P$2_P$2") (pintype "passive"))
      (node (ref "R2") (pin "P$2") (pinfunction "P$2_P$2") (pintype "passive"))
      (node (ref "TREBEL") (pin "2A") (pinfunction "2_2A") (pintype "bidirectional"))
    )
    (net (code "43") (name "Net-(TREBELA-3)") (class "Default")
      (node (ref "C10") (pin "P$2") (pinfunction "P$2_P$2") (pintype "passive"))
      (node (ref "R4") (pin "P$2") (pinfunction "P$2_P$2") (pintype "passive"))
      (node (ref "TREBEL") (pin "3A") (pinfunction "3_3A") (pintype "bidirectional"))
    )
    (net (code "44") (name "Net-(TREBELB-1)") (class "Default")
      (node (ref "C16") (pin "P$1") (pinfunction "P$1_P$1") (pintype "passive"))
      (node (ref "R7") (pin "P$2") (pinfunction "P$2_P$2") (pintype "passive"))
      (node (ref "TREBEL") (pin "1B") (pinfunction "1_1B") (pintype "bidirectional"))
    )
    (net (code "45") (name "Net-(TREBELB-2)") (class "Default")
      (node (ref "C16") (pin "P$2") (pinfunction "P$2_P$2") (pintype "passive"))
      (node (ref "C17") (pin "P$1") (pinfunction "P$1_P$1") (pintype "passive"))
      (node (ref "R8") (pin "P$2") (pinfunction "P$2_P$2") (pintype "passive"))
      (node (ref "TREBEL") (pin "2B") (pinfunction "2_2B") (pintype "bidirectional"))
    )
    (net (code "46") (name "Net-(TREBELB-3)") (class "Default")
      (node (ref "C17") (pin "P$2") (pinfunction "P$2_P$2") (pintype "passive"))
      (node (ref "R10") (pin "P$2") (pinfunction "P$2_P$2") (pintype "passive"))
      (node (ref "TREBEL") (pin "3B") (pinfunction "3_3B") (pintype "bidirectional"))
    )
    (net (code "47") (name "Net-(U1-SVR)") (class "Default")
      (node (ref "C32") (pin "P$1") (pinfunction "P$1_P$1") (pintype "passive"))
      (node (ref "U1") (pin "P$10") (pinfunction "SVR_P$10") (pintype "bidirectional"))
    )
    (net (code "48") (name "Net-(U2A-INPUT_1-)") (class "Default")
      (node (ref "U2") (pin "2") (pinfunction "INPUT_1-_2") (pintype "bidirectional"))
      (node (ref "VOL") (pin "2A") (pinfunction "2_2A") (pintype "bidirectional"))
    )
    (net (code "49") (name "Net-(U2A-OUTPUT_1)") (class "Default")
      (node (ref "C6") (pin "P$2") (pinfunction "P$2_P$2") (pintype "passive"))
      (node (ref "R15") (pin "P$2") (pinfunction "P$2_P$2") (pintype "passive"))
      (node (ref "U2") (pin "1") (pinfunction "OUTPUT_1_1") (pintype "bidirectional"))
    )
    (net (code "50") (name "Net-(U2B-INPUT_2+)") (class "Default")
      (node (ref "C11") (pin "P$1") (pinfunction "P$1_P$1") (pintype "passive"))
      (node (ref "R5") (pin "P$2") (pinfunction "P$2_P$2") (pintype "passive"))
      (node (ref "R6") (pin "P$1") (pinfunction "P$1_P$1") (pintype "passive"))
      (node (ref "U2") (pin "5") (pinfunction "INPUT_2+_5") (pintype "bidirectional"))
    )
    (net (code "51") (name "Net-(U2B-INPUT_2-)") (class "Default")
      (node (ref "R2") (pin "P$1") (pinfunction "P$1_P$1") (pintype "passive"))
      (node (ref "R3") (pin "P$2") (pinfunction "P$2_P$2") (pintype "passive"))
      (node (ref "U2") (pin "6") (pinfunction "INPUT_2-_6") (pintype "bidirectional"))
    )
    (net (code "52") (name "Net-(U2B-OUTPUT_2)") (class "Default")
      (node (ref "C12") (pin "P$1") (pinfunction "P$1_P$1") (pintype "passive"))
      (node (ref "C8") (pin "P$2") (pinfunction "P$2_P$2") (pintype "passive"))
      (node (ref "R4") (pin "P$1") (pinfunction "P$1_P$1") (pintype "passive"))
      (node (ref "U2") (pin "7") (pinfunction "OUTPUT_2_7") (pintype "bidirectional"))
    )
    (net (code "53") (name "Net-(U3A-INPUT_1-)") (class "Default")
      (node (ref "U3") (pin "2") (pinfunction "INPUT_1-_2") (pintype "bidirectional"))
      (node (ref "VOL") (pin "2B") (pinfunction "2_2B") (pintype "bidirectional"))
    )
    (net (code "54") (name "Net-(U3A-OUTPUT_1)") (class "Default")
      (node (ref "C13") (pin "P$2") (pinfunction "P$2_P$2") (pintype "passive"))
      (node (ref "R16") (pin "P$2") (pinfunction "P$2_P$2") (pintype "passive"))
      (node (ref "U3") (pin "1") (pinfunction "OUTPUT_1_1") (pintype "bidirectional"))
    )
    (net (code "55") (name "Net-(U3B-INPUT_2+)") (class "Default")
      (node (ref "C18") (pin "P$1") (pinfunction "P$1_P$1") (pintype "passive"))
      (node (ref "R11") (pin "P$2") (pinfunction "P$2_P$2") (pintype "passive"))
      (node (ref "R12") (pin "P$1") (pinfunction "P$1_P$1") (pintype "passive"))
      (node (ref "U3") (pin "5") (pinfunction "INPUT_2+_5") (pintype "bidirectional"))
    )
    (net (code "56") (name "Net-(U3B-INPUT_2-)") (class "Default")
      (node (ref "R8") (pin "P$1") (pinfunction "P$1_P$1") (pintype "passive"))
      (node (ref "R9") (pin "P$2") (pinfunction "P$2_P$2") (pintype "passive"))
      (node (ref "U3") (pin "6") (pinfunction "INPUT_2-_6") (pintype "bidirectional"))
    )
    (net (code "57") (name "Net-(U3B-OUTPUT_2)") (class "Default")
      (node (ref "C15") (pin "P$2") (pinfunction "P$2_P$2") (pintype "passive"))
      (node (ref "C19") (pin "P$1") (pinfunction "P$1_P$1") (pintype "passive"))
      (node (ref "R10") (pin "P$1") (pinfunction "P$1_P$1") (pintype "passive"))
      (node (ref "U3") (pin "7") (pinfunction "OUTPUT_2_7") (pintype "bidirectional"))
    )
    (net (code "58") (name "Net-(U4A-OUTPUT_1)") (class "Default")
      (node (ref "C27") (pin "P$2") (pinfunction "P$2_P$2") (pintype "passive"))
      (node (ref "R21") (pin "P$2") (pinfunction "P$2_P$2") (pintype "passive"))
      (node (ref "U4") (pin "1") (pinfunction "OUTPUT_1_1") (pintype "bidirectional"))
    )
    (net (code "59") (name "Net-(U4B-OUTPUT_2)") (class "Default")
      (node (ref "C28") (pin "P$2") (pinfunction "P$2_P$2") (pintype "passive"))
      (node (ref "R23") (pin "P$2") (pinfunction "P$2_P$2") (pintype "passive"))
      (node (ref "U4") (pin "7") (pinfunction "OUTPUT_2_7") (pintype "bidirectional"))
    )
    (net (code "60") (name "Net-(U5A-INPUT_1+)") (class "Default")
      (node (ref "R29") (pin "P$1") (pinfunction "P$1_P$1") (pintype "passive"))
      (node (ref "U5") (pin "3") (pinfunction "INPUT_1+_3") (pintype "bidirectional"))
    )
    (net (code "61") (name "Net-(U5A-INPUT_1-)") (class "Default")
      (node (ref "C26") (pin "P$1") (pinfunction "P$1_P$1") (pintype "passive"))
      (node (ref "R25") (pin "P$2") (pinfunction "P$2_P$2") (pintype "passive"))
      (node (ref "R26") (pin "P$2") (pinfunction "P$2_P$2") (pintype "passive"))
      (node (ref "R28") (pin "P$1") (pinfunction "P$1_P$1") (pintype "passive"))
      (node (ref "U5") (pin "2") (pinfunction "INPUT_1-_2") (pintype "bidirectional"))
    )
    (net (code "62") (name "Net-(U5B-INPUT_2+)") (class "Default")
      (node (ref "C24") (pin "P$1") (pinfunction "P$1_P$1") (pintype "passive"))
      (node (ref "R31") (pin "P$1") (pinfunction "P$1_P$1") (pintype "passive"))
      (node (ref "U5") (pin "5") (pinfunction "INPUT_2+_5") (pintype "bidirectional"))
    )
    (net (code "63") (name "Net-(U5B-INPUT_2-)") (class "Default")
      (node (ref "R30") (pin "P$2") (pinfunction "P$2_P$2") (pintype "passive"))
      (node (ref "R32") (pin "P$1") (pinfunction "P$1_P$1") (pintype "passive"))
      (node (ref "U5") (pin "6") (pinfunction "INPUT_2-_6") (pintype "bidirectional"))
    )
    (net (code "64") (name "Net-(U5B-OUTPUT_2)") (class "Default")
      (node (ref "C25") (pin "P$1") (pinfunction "P$1_P$1") (pintype "passive"))
      (node (ref "R30") (pin "P$1") (pinfunction "P$1_P$1") (pintype "passive"))
      (node (ref "U5") (pin "7") (pinfunction "OUTPUT_2_7") (pintype "bidirectional"))
    )
    (net (code "65") (name "Net-(U6A-INPUT_1+)") (class "Default")
      (node (ref "C33") (pin "P$2") (pinfunction "P$2_P$2") (pintype "passive"))
      (node (ref "C34") (pin "P$1") (pinfunction "P$1_P$1") (pintype "passive"))
      (node (ref "R33") (pin "P$2") (pinfunction "P$2_P$2") (pintype "passive"))
      (node (ref "R34") (pin "P$1") (pinfunction "P$1_P$1") (pintype "passive"))
      (node (ref "U6") (pin "3") (pinfunction "INPUT_1+_3") (pintype "bidirectional"))
    )
    (net (code "66") (name "Net-(U6A-OUTPUT_1)") (class "Default")
      (node (ref "R35") (pin "P$1") (pinfunction "P$1_P$1") (pintype "passive"))
      (node (ref "U6") (pin "1") (pinfunction "OUTPUT_1_1") (pintype "bidirectional"))
    )
    (net (code "67") (name "Net-(VOLA-1)") (class "Default")
      (node (ref "R15") (pin "P$1") (pinfunction "P$1_P$1") (pintype "passive"))
      (node (ref "VOL") (pin "1A") (pinfunction "1_1A") (pintype "bidirectional"))
    )
    (net (code "68") (name "Net-(VOLA-3)") (class "Default")
      (node (ref "R18") (pin "P$2") (pinfunction "P$2_P$2") (pintype "passive"))
      (node (ref "VOL") (pin "3A") (pinfunction "3_3A") (pintype "bidirectional"))
    )
    (net (code "69") (name "Net-(VOLB-1)") (class "Default")
      (node (ref "R17") (pin "P$2") (pinfunction "P$2_P$2") (pintype "passive"))
      (node (ref "VOL") (pin "1B") (pinfunction "1_1B") (pintype "bidirectional"))
    )
    (net (code "70") (name "Net-(VOLB-3)") (class "Default")
      (node (ref "R16") (pin "P$1") (pinfunction "P$1_P$1") (pintype "passive"))
      (node (ref "VOL") (pin "3B") (pinfunction "3_3B") (pintype "bidirectional"))
    )
    (net (code "71") (name "VGND") (class "Default")
      (node (ref "C11") (pin "P$2") (pinfunction "P$2_P$2") (pintype "passive"))
      (node (ref "C18") (pin "P$2") (pinfunction "P$2_P$2") (pintype "passive"))
      (node (ref "C24") (pin "P$2") (pinfunction "P$2_P$2") (pintype "passive"))
      (node (ref "R12") (pin "P$2") (pinfunction "P$2_P$2") (pintype "passive"))
      (node (ref "R13") (pin "P$2") (pinfunction "P$2_P$2") (pintype "passive"))
      (node (ref "R14") (pin "P$2") (pinfunction "P$2_P$2") (pintype "passive"))
      (node (ref "R17") (pin "P$1") (pinfunction "P$1_P$1") (pintype "passive"))
      (node (ref "R18") (pin "P$1") (pinfunction "P$1_P$1") (pintype "passive"))
      (node (ref "R19") (pin "P$2") (pinfunction "P$2_P$2") (pintype "passive"))
      (node (ref "R20") (pin "P$2") (pinfunction "P$2_P$2") (pintype "passive"))
      (node (ref "R22") (pin "P$1") (pinfunction "P$1_P$1") (pintype "passive"))
      (node (ref "R24") (pin "P$1") (pinfunction "P$1_P$1") (pintype "passive"))
      (node (ref "R29") (pin "P$2") (pinfunction "P$2_P$2") (pintype "passive"))
      (node (ref "R32") (pin "P$2") (pinfunction "P$2_P$2") (pintype "passive"))
      (node (ref "R35") (pin "P$2") (pinfunction "P$2_P$2") (pintype "passive"))
      (node (ref "R6") (pin "P$2") (pinfunction "P$2_P$2") (pintype "passive"))
      (node (ref "U6") (pin "2") (pinfunction "INPUT_1-_2") (pintype "bidirectional"))
    )
    (net (code "72") (name "VIN") (class "Default")
      (node (ref "C29") (pin "P$1") (pinfunction "P$1_P$1") (pintype "passive"))
      (node (ref "C31") (pin "P$1") (pinfunction "P$1_P$1") (pintype "passive"))
      (node (ref "C33") (pin "P$1") (pinfunction "P$1_P$1") (pintype "passive"))
      (node (ref "C35") (pin "P$1") (pinfunction "P$1_P$1") (pintype "passive"))
      (node (ref "J5") (pin "P$1") (pinfunction "PIN1_P$1") (pintype "bidirectional"))
      (node (ref "R11") (pin "P$1") (pinfunction "P$1_P$1") (pintype "passive"))
      (node (ref "R33") (pin "P$1") (pinfunction "P$1_P$1") (pintype "passive"))
      (node (ref "R5") (pin "P$1") (pinfunction "P$1_P$1") (pintype "passive"))
      (node (ref "U1") (pin "P$20") (pinfunction "VCC_3-4_P$20") (pintype "bidirectional"))
      (node (ref "U1") (pin "P$22") (pinfunction "MUTE_P$22") (pintype "bidirectional"))
      (node (ref "U1") (pin "P$4") (pinfunction "ST-BY_P$4") (pintype "bidirectional"))
      (node (ref "U1") (pin "P$6") (pinfunction "VCC_1-2_P$6") (pintype "bidirectional"))
      (node (ref "U2") (pin "8") (pinfunction "VCC_8") (pintype "bidirectional"))
      (node (ref "U3") (pin "8") (pinfunction "VCC_8") (pintype "bidirectional"))
      (node (ref "U4") (pin "8") (pinfunction "VCC_8") (pintype "bidirectional"))
      (node (ref "U5") (pin "8") (pinfunction "VCC_8") (pintype "bidirectional"))
      (node (ref "U6") (pin "8") (pinfunction "VCC_8") (pintype "bidirectional"))
    )
    (net (code "73") (name "unconnected-(SUB_VOLUMEA-1-Pad1A)") (class "Default")
      (node (ref "SUB_VOLUME") (pin "1A") (pinfunction "1_1A") (pintype "bidirectional"))
    )
    (net (code "74") (name "unconnected-(U1-OUT4+-PadP$21)") (class "Default")
      (node (ref "U1") (pin "P$21") (pinfunction "OUT4+_P$21") (pintype "bidirectional"))
    )
    (net (code "75") (name "unconnected-(U1-OUT4--PadP$23)") (class "Default")
      (node (ref "U1") (pin "P$23") (pinfunction "OUT4-_P$23") (pintype "bidirectional"))
    )
  )
)
